# Artemis-Nano.net
KiCad netlist of a schematic drawn in EAGLE
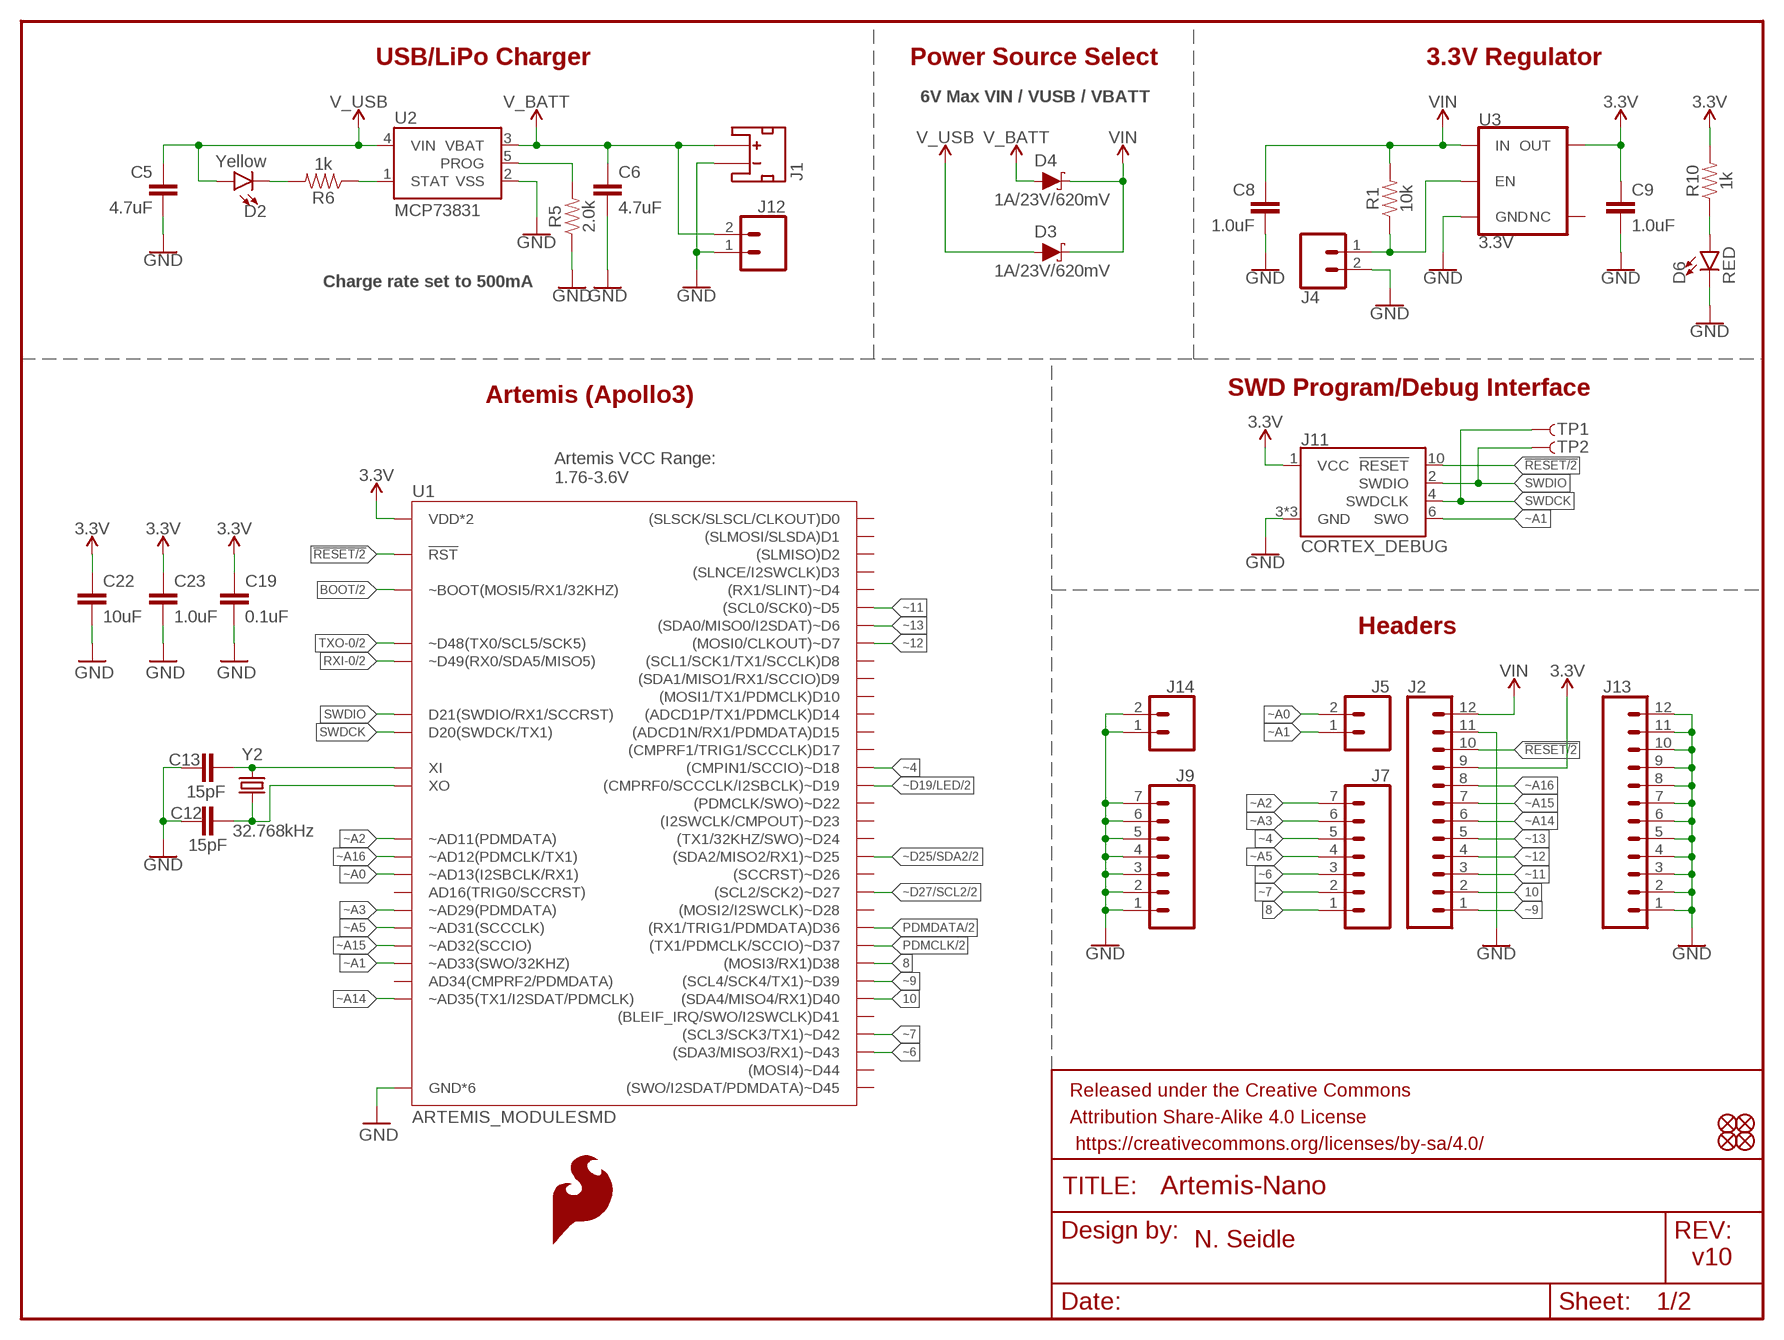
[diagram p0: schematic, sheet 1]
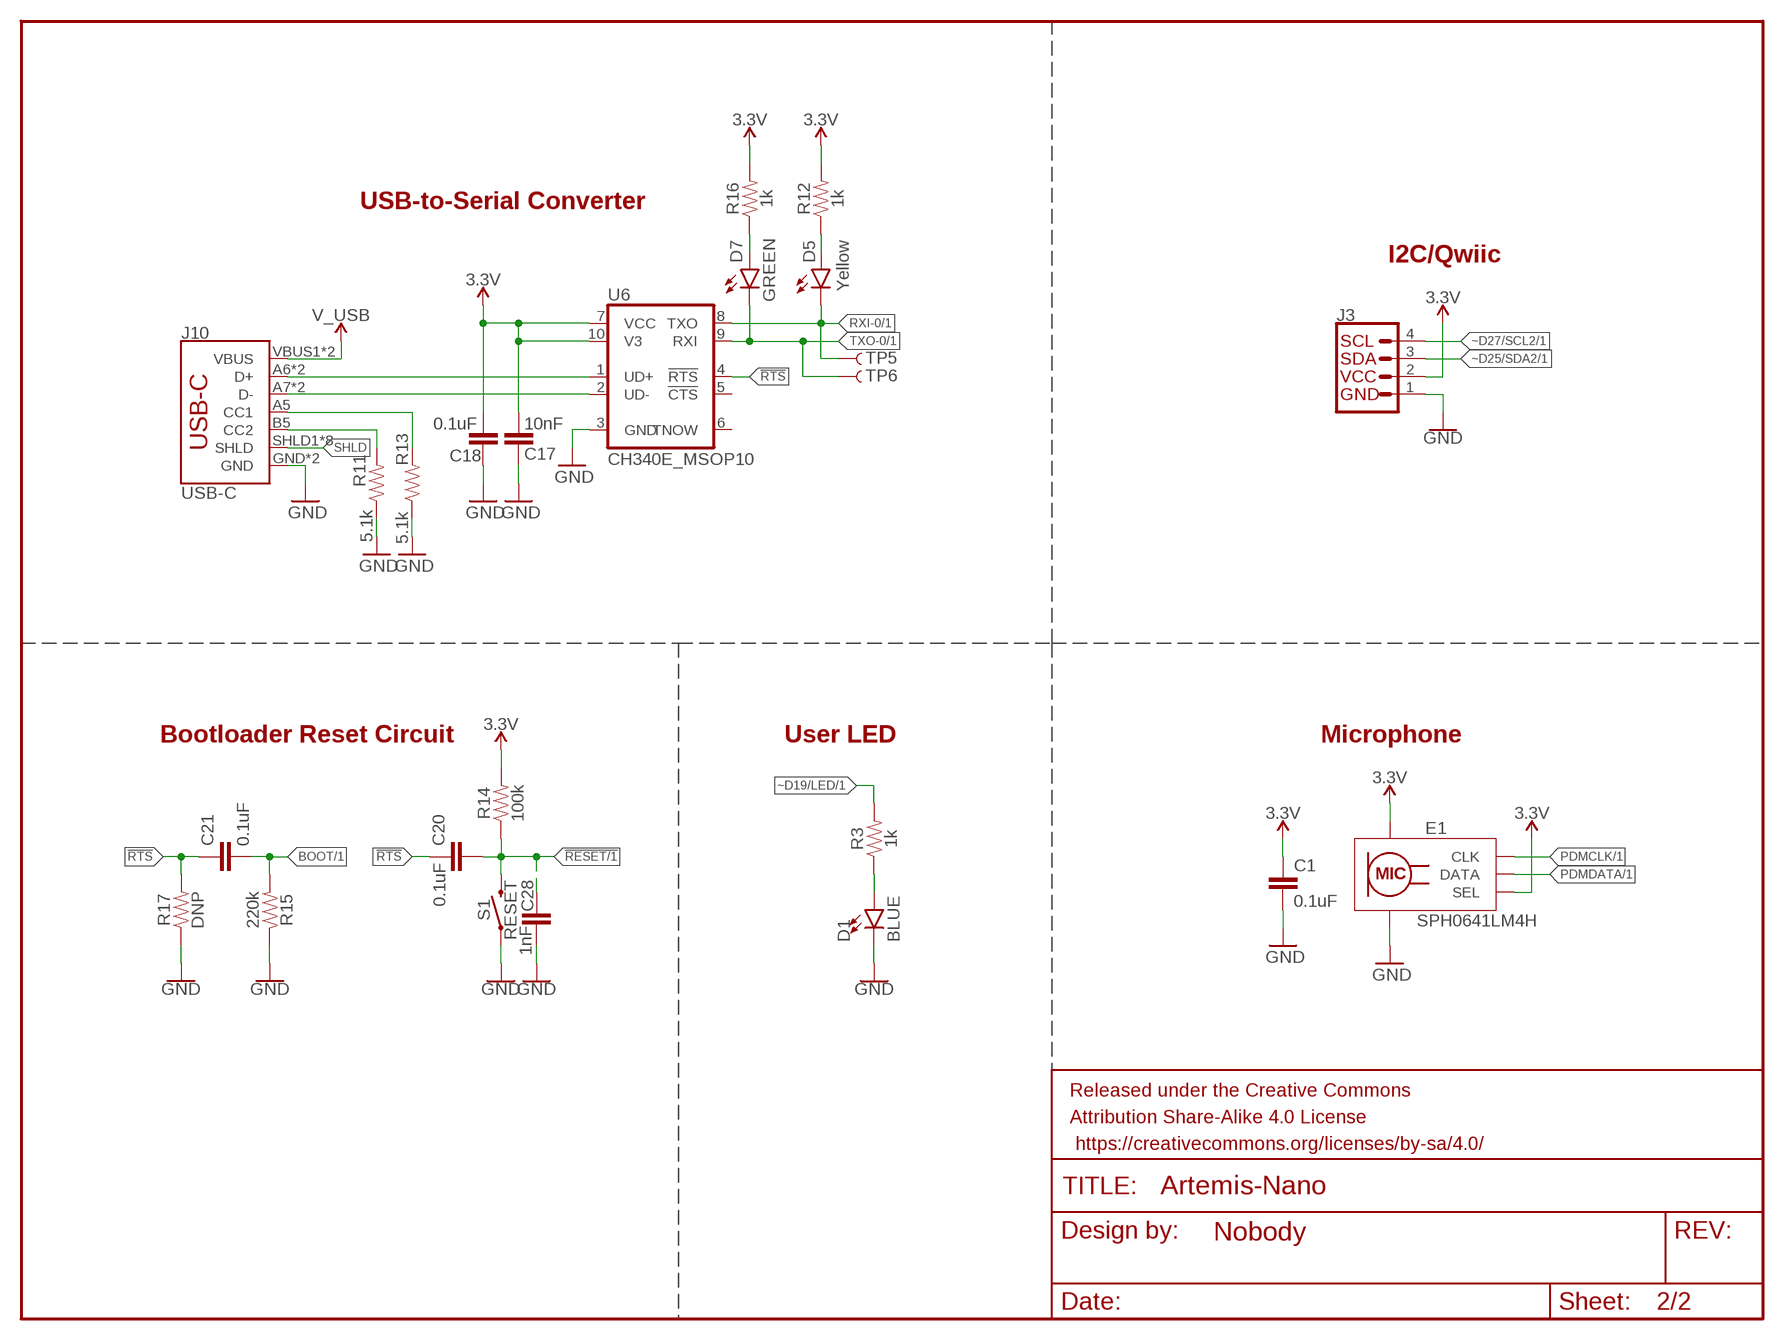
[diagram p1: schematic, sheet 2]

(export (version "E")
  (design (tool "Eeschema 10.0.6"))
  (components
    (comp (ref "C5")
      (value "4.7uF")
      (footprint "eagle-import:0603")
      (libsource (lib "eagle-import") (part "4.7UF-0603-6.3V-(10%)"))
    )
    (comp (ref "C6")
      (value "4.7uF")
      (footprint "eagle-import:0603")
      (libsource (lib "eagle-import") (part "4.7UF-0603-6.3V-(10%)"))
    )
    (comp (ref "C8")
      (value "1.0uF")
      (footprint "eagle-import:0402-TIGHT")
      (libsource (lib "eagle-import") (part "1.0UF-0402T-16V-10%"))
    )
    (comp (ref "C9")
      (value "1.0uF")
      (footprint "eagle-import:0402-TIGHT")
      (libsource (lib "eagle-import") (part "1.0UF-0402T-16V-10%"))
    )
    (comp (ref "C12")
      (value "15pF")
      (footprint "eagle-import:0603")
      (libsource (lib "eagle-import") (part "15PF-0603-50V-5%"))
    )
    (comp (ref "C13")
      (value "15pF")
      (footprint "eagle-import:0603")
      (libsource (lib "eagle-import") (part "15PF-0603-50V-5%"))
    )
    (comp (ref "C19")
      (value "0.1uF")
      (footprint "eagle-import:0402-TIGHT")
      (libsource (lib "eagle-import") (part "0.1UF-0402T-16V-10%"))
    )
    (comp (ref "C22")
      (value "10uF")
      (footprint "eagle-import:0603")
      (libsource (lib "eagle-import") (part "10UF-0603-6.3V-20%"))
    )
    (comp (ref "C23")
      (value "1.0uF")
      (footprint "eagle-import:0402-TIGHT")
      (libsource (lib "eagle-import") (part "1.0UF-0402T-16V-10%"))
    )
    (comp (ref "D2")
      (value "Yellow")
      (footprint "eagle-import:LED-0603")
      (libsource (lib "eagle-import") (part "LED-YELLOW0603"))
    )
    (comp (ref "D3")
      (value "1A/23V/620mV")
      (footprint "eagle-import:SOD-323")
      (libsource (lib "eagle-import") (part "DIODE-SCHOTTKY-BAT20J"))
    )
    (comp (ref "D4")
      (value "1A/23V/620mV")
      (footprint "eagle-import:SOD-323")
      (libsource (lib "eagle-import") (part "DIODE-SCHOTTKY-BAT20J"))
    )
    (comp (ref "D6")
      (value "RED")
      (footprint "eagle-import:LED-0603")
      (libsource (lib "eagle-import") (part "LED-RED0603"))
    )
    (comp (ref "FD1")
      (value "FIDUCIALUFIDUCIAL")
      (footprint "eagle-import:FIDUCIAL-MICRO")
      (libsource (lib "eagle-import") (part "FIDUCIALUFIDUCIAL"))
    )
    (comp (ref "FD2")
      (value "FIDUCIALUFIDUCIAL")
      (footprint "eagle-import:FIDUCIAL-MICRO")
      (libsource (lib "eagle-import") (part "FIDUCIALUFIDUCIAL"))
    )
    (comp (ref "FD3")
      (value "FIDUCIALUFIDUCIAL")
      (footprint "eagle-import:FIDUCIAL-MICRO")
      (libsource (lib "eagle-import") (part "FIDUCIALUFIDUCIAL"))
    )
    (comp (ref "FD4")
      (value "FIDUCIALUFIDUCIAL")
      (footprint "eagle-import:FIDUCIAL-MICRO")
      (libsource (lib "eagle-import") (part "FIDUCIALUFIDUCIAL"))
    )
    (comp (ref "FRAME1")
      (value "FRAME-LETTER")
      (footprint "eagle-import:CREATIVE_COMMONS")
      (libsource (lib "eagle-import") (part "FRAME-LETTER"))
    )
    (comp (ref "J1")
      (value "JST_2MM_MALE")
      (footprint "eagle-import:JST-2-SMD")
      (libsource (lib "eagle-import") (part "JST_2MM_MALE"))
    )
    (comp (ref "J2")
      (value "CONN_12NO_SILK")
      (footprint "eagle-import:1X12_NO_SILK")
      (libsource (lib "eagle-import") (part "CONN_12NO_SILK"))
    )
    (comp (ref "J4")
      (value "CONN_021X02_NO_SILK")
      (footprint "eagle-import:1X02_NO_SILK")
      (libsource (lib "eagle-import") (part "CONN_021X02_NO_SILK"))
    )
    (comp (ref "J5")
      (value "CONN_021X02_NO_SILK")
      (footprint "eagle-import:1X02_NO_SILK")
      (libsource (lib "eagle-import") (part "CONN_021X02_NO_SILK"))
    )
    (comp (ref "J7")
      (value "CONN_07NO_SILK")
      (footprint "eagle-import:1X07_NO_SILK")
      (libsource (lib "eagle-import") (part "CONN_07NO_SILK"))
    )
    (comp (ref "J9")
      (value "CONN_07NO_SILK")
      (footprint "eagle-import:1X07_NO_SILK")
      (libsource (lib "eagle-import") (part "CONN_07NO_SILK"))
    )
    (comp (ref "J11")
      (value "CORTEX_DEBUG")
      (footprint "eagle-import:2X5-PTH-1.27MM-NO_SILK")
      (libsource (lib "eagle-import") (part "CORTEX_DEBUG_MINIMUM_PTH_NS"))
    )
    (comp (ref "J12")
      (value "CONN_021X02_NO_SILK")
      (footprint "eagle-import:1X02_NO_SILK")
      (libsource (lib "eagle-import") (part "CONN_021X02_NO_SILK"))
    )
    (comp (ref "J13")
      (value "CONN_12NO_SILK")
      (footprint "eagle-import:1X12_NO_SILK")
      (libsource (lib "eagle-import") (part "CONN_12NO_SILK"))
    )
    (comp (ref "J14")
      (value "CONN_021X02_NO_SILK")
      (footprint "eagle-import:1X02_NO_SILK")
      (libsource (lib "eagle-import") (part "CONN_021X02_NO_SILK"))
    )
    (comp (ref "LOGO1")
      (value "SFE_LOGO_FLAME.1_INCH")
      (footprint "eagle-import:SFE_LOGO_FLAME_.1")
      (libsource (lib "eagle-import") (part "SFE_LOGO_FLAME.1_INCH"))
    )
    (comp (ref "LOGO4")
      (value "SFE_LOGO_FLAME.1_INCH")
      (footprint "eagle-import:SFE_LOGO_FLAME_.1")
      (libsource (lib "eagle-import") (part "SFE_LOGO_FLAME.1_INCH"))
    )
    (comp (ref "R1")
      (value "10k")
      (footprint "eagle-import:0603")
      (libsource (lib "eagle-import") (part "10KOHM-0603-1/10W-1%"))
    )
    (comp (ref "R5")
      (value "2.0k")
      (footprint "eagle-import:0603")
      (libsource (lib "eagle-import") (part "2.0KOHM-0603-1/10W-5%"))
    )
    (comp (ref "R6")
      (value "1k")
      (footprint "eagle-import:0603")
      (libsource (lib "eagle-import") (part "1KOHM-0603-1/10W-1%"))
    )
    (comp (ref "R10")
      (value "1k")
      (footprint "eagle-import:0603")
      (libsource (lib "eagle-import") (part "1KOHM-0603-1/10W-1%"))
    )
    (comp (ref "TP1")
      (value "TEST-POINT3X5")
      (footprint "eagle-import:PAD.03X.05")
      (libsource (lib "eagle-import") (part "TEST-POINT3X5"))
    )
    (comp (ref "TP2")
      (value "TEST-POINT3X5")
      (footprint "eagle-import:PAD.03X.05")
      (libsource (lib "eagle-import") (part "TEST-POINT3X5"))
    )
    (comp (ref "U1")
      (value "ARTEMIS_MODULESMD")
      (footprint "eagle-import:ARTEMIS_FP")
      (libsource (lib "eagle-import") (part "ARTEMIS_MODULESMD"))
    )
    (comp (ref "U2")
      (value "MCP73831")
      (footprint "eagle-import:SOT23-5")
      (libsource (lib "eagle-import") (part "MCP73831"))
    )
    (comp (ref "U3")
      (value "3.3V")
      (footprint "eagle-import:SOT23-5")
      (libsource (lib "eagle-import") (part "V_REG_AP2112K-3.3V"))
    )
    (comp (ref "Y2")
      (value "32.768kHz")
      (footprint "eagle-import:CRYSTAL-SMD-3.2X1.5MM")
      (libsource (lib "eagle-import") (part "CRYSTAL-32.768KHZSMD-3.2X1.5"))
    )
    (comp (ref "C1")
      (value "0.1uF")
      (footprint "eagle-import:0402-TIGHT")
      (libsource (lib "eagle-import") (part "0.1UF-0402T-16V-10%"))
    )
    (comp (ref "C17")
      (value "10nF")
      (footprint "eagle-import:0603")
      (libsource (lib "eagle-import") (part "10NF-0603-50V-10%"))
    )
    (comp (ref "C18")
      (value "0.1uF")
      (footprint "eagle-import:0603")
      (libsource (lib "eagle-import") (part "0.1UF-0603-25V-(+80/-20%)"))
    )
    (comp (ref "C20")
      (value "0.1uF")
      (footprint "eagle-import:0603")
      (libsource (lib "eagle-import") (part "0.1UF-0603-25V-5%"))
    )
    (comp (ref "C21")
      (value "0.1uF")
      (footprint "eagle-import:0603")
      (libsource (lib "eagle-import") (part "0.1UF-0603-25V-5%"))
    )
    (comp (ref "C28")
      (value "1nF")
      (footprint "eagle-import:0603")
      (libsource (lib "eagle-import") (part "1.0NF/1000PF-0603-50V-10%"))
    )
    (comp (ref "D1")
      (value "BLUE")
      (footprint "eagle-import:LED-0603")
      (libsource (lib "eagle-import") (part "LED-BLUE0603"))
    )
    (comp (ref "D5")
      (value "Yellow")
      (footprint "eagle-import:LED-0603")
      (libsource (lib "eagle-import") (part "LED-YELLOW0603"))
    )
    (comp (ref "D7")
      (value "GREEN")
      (footprint "eagle-import:LED-0603")
      (libsource (lib "eagle-import") (part "LED-GREEN0603"))
    )
    (comp (ref "E1")
      (value "SPH0641LM4H")
      (footprint "eagle-import:SPH0641LM4H-1_MICROPHONE")
      (libsource (lib "eagle-import") (part "SPH0641LM4H-1_MICROPHONE"))
    )
    (comp (ref "FRAME2")
      (value "FRAME-LETTERNO_PACKAGE")
      (footprint "eagle-import:DUMMY")
      (fields (field (name "DESIGNER") "Nobody"))
      (libsource (lib "eagle-import") (part "FRAME-LETTERNO_PACKAGE"))
    )
    (comp (ref "J3")
      (value "QWIIC_CONNECTORJS-1MM")
      (footprint "eagle-import:JST04_1MM_RA")
      (libsource (lib "eagle-import") (part "QWIIC_CONNECTORJS-1MM"))
    )
    (comp (ref "J10")
      (value "USB-C")
      (footprint "eagle-import:USB-C-16P")
      (libsource (lib "eagle-import") (part "USB_C"))
    )
    (comp (ref "R3")
      (value "1k")
      (footprint "eagle-import:0603")
      (libsource (lib "eagle-import") (part "1KOHM-0603-1/10W-1%"))
    )
    (comp (ref "R11")
      (value "5.1k")
      (footprint "eagle-import:0603")
      (libsource (lib "eagle-import") (part "5.1KOHM5.1KOHM-0603-1/10W-1%"))
    )
    (comp (ref "R12")
      (value "1k")
      (footprint "eagle-import:0603")
      (libsource (lib "eagle-import") (part "1KOHM-0603-1/10W-1%"))
    )
    (comp (ref "R13")
      (value "5.1k")
      (footprint "eagle-import:0603")
      (libsource (lib "eagle-import") (part "5.1KOHM5.1KOHM-0603-1/10W-1%"))
    )
    (comp (ref "R14")
      (value "100k")
      (footprint "eagle-import:0603")
      (libsource (lib "eagle-import") (part "100KOHM-0603-1/10W-1%"))
    )
    (comp (ref "R15")
      (value "220k")
      (footprint "eagle-import:0603")
      (libsource (lib "eagle-import") (part "220KOHM-0603-1/10W-1%"))
    )
    (comp (ref "R16")
      (value "1k")
      (footprint "eagle-import:0603")
      (libsource (lib "eagle-import") (part "1KOHM-0603-1/10W-1%"))
    )
    (comp (ref "R17")
      (value "DNP")
      (footprint "eagle-import:0603")
      (libsource (lib "eagle-import") (part "1MOHM-0603-1/4W-5%"))
    )
    (comp (ref "S1")
      (value "RESET")
      (footprint "eagle-import:TACTILE_SWITCH_SMD_4.6X2.8MM")
      (libsource (lib "eagle-import") (part "MOMENTARY-SWITCH-SPST-SMD-4.6X2.8MM"))
    )
    (comp (ref "TP5")
      (value "TEST-POINT3X5")
      (footprint "eagle-import:PAD.03X.05")
      (libsource (lib "eagle-import") (part "TEST-POINT3X5"))
    )
    (comp (ref "TP6")
      (value "TEST-POINT3X5")
      (footprint "eagle-import:PAD.03X.05")
      (libsource (lib "eagle-import") (part "TEST-POINT3X5"))
    )
    (comp (ref "U6")
      (value "CH340E_MSOP10")
      (footprint "eagle-import:MSOP10")
      (libsource (lib "eagle-import") (part "CH340E_MSOP10"))
    )
  )
  (nets
    (net (code "1") (name "3.3V") (class "Default")
      (node (ref "C1") (pin "1") (pinfunction "1_1") (pintype "passive"))
      (node (ref "C17") (pin "1") (pinfunction "1_1") (pintype "passive"))
      (node (ref "C18") (pin "1") (pinfunction "1_1") (pintype "passive"))
      (node (ref "C19") (pin "2") (pinfunction "2_2") (pintype "passive"))
      (node (ref "C22") (pin "1") (pinfunction "1_1") (pintype "passive"))
      (node (ref "C23") (pin "1") (pinfunction "1_1") (pintype "passive"))
      (node (ref "C9") (pin "1") (pinfunction "1_1") (pintype "passive"))
      (node (ref "E1") (pin "2") (pinfunction "SEL_2") (pintype "input"))
      (node (ref "E1") (pin "5") (pinfunction "VDD_5") (pintype "power_in"))
      (node (ref "J11") (pin "1") (pinfunction "VCC_1") (pintype "bidirectional"))
      (node (ref "J2") (pin "9") (pinfunction "9_9") (pintype "passive"))
      (node (ref "J3") (pin "2") (pinfunction "2_2") (pintype "power_in"))
      (node (ref "R10") (pin "2") (pinfunction "2_2") (pintype "passive"))
      (node (ref "R12") (pin "2") (pinfunction "2_2") (pintype "passive"))
      (node (ref "R14") (pin "2") (pinfunction "2_2") (pintype "passive"))
      (node (ref "R16") (pin "2") (pinfunction "2_2") (pintype "passive"))
      (node (ref "U1") (pin "VDD@36") (pinfunction "VDD*2_VDD@36") (pintype "bidirectional"))
      (node (ref "U1") (pin "VDD@37") (pinfunction "VDD*2_VDD@37") (pintype "bidirectional"))
      (node (ref "U3") (pin "5") (pinfunction "OUT_5") (pintype "passive"))
      (node (ref "U6") (pin "10") (pinfunction "V3_10") (pintype "bidirectional"))
      (node (ref "U6") (pin "7") (pinfunction "VCC_7") (pintype "bidirectional"))
    )
    (net (code "2") (name "8") (class "Default")
      (node (ref "J7") (pin "1") (pinfunction "1_1") (pintype "passive"))
      (node (ref "U1") (pin "D38") (pinfunction "(MOSI3/RX1)D38_D38") (pintype "bidirectional"))
    )
    (net (code "3") (name "10") (class "Default")
      (node (ref "J2") (pin "2") (pinfunction "2_2") (pintype "passive"))
      (node (ref "U1") (pin "D40") (pinfunction "(SDA4/MISO4/RX1)D40_D40") (pintype "bidirectional"))
    )
    (net (code "4") (name "BOOT") (class "Default")
      (node (ref "C21") (pin "2") (pinfunction "2_2") (pintype "passive"))
      (node (ref "R15") (pin "2") (pinfunction "2_2") (pintype "passive"))
      (node (ref "U1") (pin "BOOT") (pinfunction "~{BOOT(MOSI5/RX1/32KHZ})_BOOT") (pintype "bidirectional"))
    )
    (net (code "5") (name "GND") (class "Default")
      (node (ref "C1") (pin "2") (pinfunction "2_2") (pintype "passive"))
      (node (ref "C12") (pin "1") (pinfunction "1_1") (pintype "passive"))
      (node (ref "C13") (pin "1") (pinfunction "1_1") (pintype "passive"))
      (node (ref "C17") (pin "2") (pinfunction "2_2") (pintype "passive"))
      (node (ref "C18") (pin "2") (pinfunction "2_2") (pintype "passive"))
      (node (ref "C19") (pin "1") (pinfunction "1_1") (pintype "passive"))
      (node (ref "C22") (pin "2") (pinfunction "2_2") (pintype "passive"))
      (node (ref "C23") (pin "2") (pinfunction "2_2") (pintype "passive"))
      (node (ref "C28") (pin "2") (pinfunction "2_2") (pintype "passive"))
      (node (ref "C5") (pin "2") (pinfunction "2_2") (pintype "passive"))
      (node (ref "C6") (pin "2") (pinfunction "2_2") (pintype "passive"))
      (node (ref "C8") (pin "2") (pinfunction "2_2") (pintype "passive"))
      (node (ref "C9") (pin "2") (pinfunction "2_2") (pintype "passive"))
      (node (ref "D1") (pin "C") (pinfunction "C_C") (pintype "passive"))
      (node (ref "D6") (pin "C") (pinfunction "C_C") (pintype "passive"))
      (node (ref "E1") (pin "3") (pinfunction "GND_3") (pintype "power_in"))
      (node (ref "E1") (pin "6") (pinfunction "GND_6") (pintype "power_in"))
      (node (ref "E1") (pin "7") (pinfunction "GND_7") (pintype "power_in"))
      (node (ref "E1") (pin "8") (pinfunction "GND_8") (pintype "power_in"))
      (node (ref "J1") (pin "1") (pinfunction "-_1") (pintype "bidirectional"))
      (node (ref "J10") (pin "GND") (pinfunction "GND_GND") (pintype "bidirectional"))
      (node (ref "J10") (pin "GND2") (pinfunction "GND_GND2") (pintype "bidirectional"))
      (node (ref "J11") (pin "3") (pinfunction "GND_3") (pintype "bidirectional"))
      (node (ref "J11") (pin "5") (pinfunction "GND_5") (pintype "bidirectional"))
      (node (ref "J11") (pin "9") (pinfunction "GND_9") (pintype "bidirectional"))
      (node (ref "J12") (pin "1") (pinfunction "1_1") (pintype "passive"))
      (node (ref "J13") (pin "1") (pinfunction "1_1") (pintype "passive"))
      (node (ref "J13") (pin "10") (pinfunction "10_10") (pintype "passive"))
      (node (ref "J13") (pin "11") (pinfunction "11_11") (pintype "passive"))
      (node (ref "J13") (pin "12") (pinfunction "12_12") (pintype "passive"))
      (node (ref "J13") (pin "2") (pinfunction "2_2") (pintype "passive"))
      (node (ref "J13") (pin "3") (pinfunction "3_3") (pintype "passive"))
      (node (ref "J13") (pin "4") (pinfunction "4_4") (pintype "passive"))
      (node (ref "J13") (pin "5") (pinfunction "5_5") (pintype "passive"))
      (node (ref "J13") (pin "6") (pinfunction "6_6") (pintype "passive"))
      (node (ref "J13") (pin "7") (pinfunction "7_7") (pintype "passive"))
      (node (ref "J13") (pin "8") (pinfunction "8_8") (pintype "passive"))
      (node (ref "J13") (pin "9") (pinfunction "9_9") (pintype "passive"))
      (node (ref "J14") (pin "1") (pinfunction "1_1") (pintype "passive"))
      (node (ref "J14") (pin "2") (pinfunction "2_2") (pintype "passive"))
      (node (ref "J2") (pin "11") (pinfunction "11_11") (pintype "passive"))
      (node (ref "J3") (pin "1") (pinfunction "1_1") (pintype "power_in"))
      (node (ref "J4") (pin "2") (pinfunction "2_2") (pintype "passive"))
      (node (ref "J9") (pin "1") (pinfunction "1_1") (pintype "passive"))
      (node (ref "J9") (pin "2") (pinfunction "2_2") (pintype "passive"))
      (node (ref "J9") (pin "3") (pinfunction "3_3") (pintype "passive"))
      (node (ref "J9") (pin "4") (pinfunction "4_4") (pintype "passive"))
      (node (ref "J9") (pin "5") (pinfunction "5_5") (pintype "passive"))
      (node (ref "J9") (pin "6") (pinfunction "6_6") (pintype "passive"))
      (node (ref "J9") (pin "7") (pinfunction "7_7") (pintype "passive"))
      (node (ref "R11") (pin "1") (pinfunction "1_1") (pintype "passive"))
      (node (ref "R13") (pin "1") (pinfunction "1_1") (pintype "passive"))
      (node (ref "R15") (pin "1") (pinfunction "1_1") (pintype "passive"))
      (node (ref "R17") (pin "1") (pinfunction "1_1") (pintype "passive"))
      (node (ref "R5") (pin "1") (pinfunction "1_1") (pintype "passive"))
      (node (ref "S1") (pin "1") (pinfunction "1_1") (pintype "passive"))
      (node (ref "S1") (pin "2") (pinfunction "1_2") (pintype "passive"))
      (node (ref "U1") (pin "GND@1") (pinfunction "GND*6_GND@1") (pintype "bidirectional"))
      (node (ref "U1") (pin "GND@22") (pinfunction "GND*6_GND@22") (pintype "bidirectional"))
      (node (ref "U1") (pin "GND@38") (pinfunction "GND*6_GND@38") (pintype "bidirectional"))
      (node (ref "U1") (pin "GND@39") (pinfunction "GND*6_GND@39") (pintype "bidirectional"))
      (node (ref "U1") (pin "GND@47") (pinfunction "GND*6_GND@47") (pintype "bidirectional"))
      (node (ref "U1") (pin "GND@59") (pinfunction "GND*6_GND@59") (pintype "bidirectional"))
      (node (ref "U2") (pin "2") (pinfunction "VSS_2") (pintype "power_in"))
      (node (ref "U3") (pin "2") (pinfunction "GND_2") (pintype "input"))
      (node (ref "U6") (pin "3") (pinfunction "GND_3") (pintype "bidirectional"))
    )
    (net (code "6") (name "Net-(D1-PadA)") (class "Default")
      (node (ref "D1") (pin "A") (pinfunction "A_A") (pintype "passive"))
      (node (ref "R3") (pin "1") (pinfunction "1_1") (pintype "passive"))
    )
    (net (code "7") (name "Net-(D2-PadC)") (class "Default")
      (node (ref "D2") (pin "C") (pinfunction "C_C") (pintype "passive"))
      (node (ref "R6") (pin "2") (pinfunction "2_2") (pintype "passive"))
    )
    (net (code "8") (name "Net-(D5-PadA)") (class "Default")
      (node (ref "D5") (pin "A") (pinfunction "A_A") (pintype "passive"))
      (node (ref "R12") (pin "1") (pinfunction "1_1") (pintype "passive"))
    )
    (net (code "9") (name "Net-(D6-PadA)") (class "Default")
      (node (ref "D6") (pin "A") (pinfunction "A_A") (pintype "passive"))
      (node (ref "R10") (pin "1") (pinfunction "1_1") (pintype "passive"))
    )
    (net (code "10") (name "Net-(D7-PadA)") (class "Default")
      (node (ref "D7") (pin "A") (pinfunction "A_A") (pintype "passive"))
      (node (ref "R16") (pin "1") (pinfunction "1_1") (pintype "passive"))
    )
    (net (code "11") (name "Net-(J10-CC1)") (class "Default")
      (node (ref "J10") (pin "A5") (pinfunction "CC1_A5") (pintype "bidirectional"))
      (node (ref "R13") (pin "2") (pinfunction "2_2") (pintype "passive"))
    )
    (net (code "12") (name "Net-(J10-CC2)") (class "Default")
      (node (ref "J10") (pin "B5") (pinfunction "CC2_B5") (pintype "bidirectional"))
      (node (ref "R11") (pin "2") (pinfunction "2_2") (pintype "passive"))
    )
    (net (code "13") (name "Net-(U2-PROG)") (class "Default")
      (node (ref "R5") (pin "2") (pinfunction "2_2") (pintype "passive"))
      (node (ref "U2") (pin "5") (pinfunction "PROG_5") (pintype "input"))
    )
    (net (code "14") (name "Net-(U2-STAT)") (class "Default")
      (node (ref "R6") (pin "1") (pinfunction "1_1") (pintype "passive"))
      (node (ref "U2") (pin "1") (pinfunction "STAT_1") (pintype "output"))
    )
    (net (code "15") (name "Net-(U3-EN)") (class "Default")
      (node (ref "J4") (pin "1") (pinfunction "1_1") (pintype "passive"))
      (node (ref "R1") (pin "1") (pinfunction "1_1") (pintype "passive"))
      (node (ref "U3") (pin "3") (pinfunction "EN_3") (pintype "input"))
    )
    (net (code "16") (name "Net-(U6-UD+)") (class "Default")
      (node (ref "J10") (pin "A6") (pinfunction "D+_A6") (pintype "bidirectional"))
      (node (ref "J10") (pin "B6") (pinfunction "D+_B6") (pintype "bidirectional"))
      (node (ref "U6") (pin "1") (pinfunction "UD+_1") (pintype "bidirectional"))
    )
    (net (code "17") (name "Net-(U6-UD-)") (class "Default")
      (node (ref "J10") (pin "A7") (pinfunction "D-_A7") (pintype "bidirectional"))
      (node (ref "J10") (pin "B7") (pinfunction "D-_B7") (pintype "bidirectional"))
      (node (ref "U6") (pin "2") (pinfunction "UD-_2") (pintype "bidirectional"))
    )
    (net (code "18") (name "Net-(Y2-1)") (class "Default")
      (node (ref "C13") (pin "2") (pinfunction "2_2") (pintype "passive"))
      (node (ref "U1") (pin "XI") (pinfunction "XI_XI") (pintype "bidirectional"))
      (node (ref "Y2") (pin "P$1") (pinfunction "1_P$1") (pintype "passive"))
    )
    (net (code "19") (name "Net-(Y2-2)") (class "Default")
      (node (ref "C12") (pin "2") (pinfunction "2_2") (pintype "passive"))
      (node (ref "U1") (pin "XO") (pinfunction "XO_XO") (pintype "bidirectional"))
      (node (ref "Y2") (pin "P$2") (pinfunction "2_P$2") (pintype "passive"))
    )
    (net (code "20") (name "PDMCLK") (class "Default")
      (node (ref "E1") (pin "4") (pinfunction "CLK_4") (pintype "input"))
      (node (ref "U1") (pin "~D37") (pinfunction "(TX1/PDMCLK/SCCIO)~{D37}_~D37") (pintype "bidirectional"))
    )
    (net (code "21") (name "PDMDATA") (class "Default")
      (node (ref "E1") (pin "1") (pinfunction "DATA_1") (pintype "output"))
      (node (ref "U1") (pin "D36") (pinfunction "(RX1/TRIG1/PDMDATA)D36_D36") (pintype "bidirectional"))
    )
    (net (code "22") (name "RXI-0") (class "Default")
      (node (ref "D5") (pin "C") (pinfunction "C_C") (pintype "passive"))
      (node (ref "TP5") (pin "P$1") (pinfunction "1_P$1") (pintype "bidirectional"))
      (node (ref "U1") (pin "RXI-0") (pinfunction "~{D49(RX0/SDA5/MISO5})_RXI-0") (pintype "bidirectional"))
      (node (ref "U6") (pin "8") (pinfunction "TXO_8") (pintype "bidirectional"))
    )
    (net (code "23") (name "SHLD") (class "Default")
      (node (ref "J10") (pin "SHLD1") (pinfunction "SHLD_SHLD1") (pintype "bidirectional"))
      (node (ref "J10") (pin "SHLD2") (pinfunction "SHLD_SHLD2") (pintype "bidirectional"))
      (node (ref "J10") (pin "SHLD3") (pinfunction "SHLD_SHLD3") (pintype "bidirectional"))
      (node (ref "J10") (pin "SHLD4") (pinfunction "SHLD_SHLD4") (pintype "bidirectional"))
      (node (ref "J10") (pin "SHLD5") (pinfunction "SHLD_SHLD5") (pintype "bidirectional"))
      (node (ref "J10") (pin "SHLD6") (pinfunction "SHLD_SHLD6") (pintype "bidirectional"))
      (node (ref "J10") (pin "SHLD7") (pinfunction "SHLD_SHLD7") (pintype "bidirectional"))
      (node (ref "J10") (pin "SHLD8") (pinfunction "SHLD_SHLD8") (pintype "bidirectional"))
    )
    (net (code "24") (name "SWDCK") (class "Default")
      (node (ref "J11") (pin "4") (pinfunction "SWDCLK_4") (pintype "bidirectional"))
      (node (ref "TP1") (pin "P$1") (pinfunction "1_P$1") (pintype "bidirectional"))
      (node (ref "U1") (pin "SWDCK") (pinfunction "D20(SWDCK/TX1)_SWDCK") (pintype "bidirectional"))
    )
    (net (code "25") (name "SWDIO") (class "Default")
      (node (ref "J11") (pin "2") (pinfunction "SWDIO_2") (pintype "bidirectional"))
      (node (ref "TP2") (pin "P$1") (pinfunction "1_P$1") (pintype "bidirectional"))
      (node (ref "U1") (pin "SWDIO") (pinfunction "D21(SWDIO/RX1/SCCRST)_SWDIO") (pintype "bidirectional"))
    )
    (net (code "26") (name "TXO-0") (class "Default")
      (node (ref "D7") (pin "C") (pinfunction "C_C") (pintype "passive"))
      (node (ref "TP6") (pin "P$1") (pinfunction "1_P$1") (pintype "bidirectional"))
      (node (ref "U1") (pin "TXO-0") (pinfunction "~{D48(TX0/SCL5/SCK5})_TXO-0") (pintype "bidirectional"))
      (node (ref "U6") (pin "9") (pinfunction "RXI_9") (pintype "bidirectional"))
    )
    (net (code "27") (name "VIN") (class "Default")
      (node (ref "C8") (pin "1") (pinfunction "1_1") (pintype "passive"))
      (node (ref "D3") (pin "C") (pinfunction "C_C") (pintype "passive"))
      (node (ref "D4") (pin "C") (pinfunction "C_C") (pintype "passive"))
      (node (ref "J2") (pin "12") (pinfunction "12_12") (pintype "passive"))
      (node (ref "R1") (pin "2") (pinfunction "2_2") (pintype "passive"))
      (node (ref "U3") (pin "1") (pinfunction "IN_1") (pintype "input"))
    )
    (net (code "28") (name "V_BATT") (class "Default")
      (node (ref "C6") (pin "1") (pinfunction "1_1") (pintype "passive"))
      (node (ref "D4") (pin "A") (pinfunction "A_A") (pintype "passive"))
      (node (ref "J1") (pin "2") (pinfunction "+_2") (pintype "bidirectional"))
      (node (ref "J12") (pin "2") (pinfunction "2_2") (pintype "passive"))
      (node (ref "U2") (pin "3") (pinfunction "VBAT_3") (pintype "power_in"))
    )
    (net (code "29") (name "V_USB") (class "Default")
      (node (ref "C5") (pin "1") (pinfunction "1_1") (pintype "passive"))
      (node (ref "D2") (pin "A") (pinfunction "A_A") (pintype "passive"))
      (node (ref "D3") (pin "A") (pinfunction "A_A") (pintype "passive"))
      (node (ref "J10") (pin "VBUS1") (pinfunction "VBUS_VBUS1") (pintype "bidirectional"))
      (node (ref "J10") (pin "VBUS2") (pinfunction "VBUS_VBUS2") (pintype "bidirectional"))
      (node (ref "U2") (pin "4") (pinfunction "VIN_4") (pintype "power_in"))
    )
    (net (code "30") (name "unconnected-(J1-PAD1-PadNC1)") (class "Default")
      (node (ref "J1") (pin "NC1") (pinfunction "PAD1_NC1") (pintype "bidirectional"))
    )
    (net (code "31") (name "unconnected-(J1-PAD2-PadNC2)") (class "Default")
      (node (ref "J1") (pin "NC2") (pinfunction "PAD2_NC2") (pintype "bidirectional"))
    )
    (net (code "32") (name "unconnected-(U1-(ADCD1N{slash}RX1{slash}PDMDATA)D15-PadD15)") (class "Default")
      (node (ref "U1") (pin "D15") (pinfunction "(ADCD1N/RX1/PDMDATA)D15_D15") (pintype "bidirectional"))
    )
    (net (code "33") (name "unconnected-(U1-(ADCD1P{slash}TX1{slash}PDMCLK)D14-PadD14)") (class "Default")
      (node (ref "U1") (pin "D14") (pinfunction "(ADCD1P/TX1/PDMCLK)D14_D14") (pintype "bidirectional"))
    )
    (net (code "34") (name "unconnected-(U1-(BLEIF_IRQ{slash}SWO{slash}I2SWCLK)D41-PadD41)") (class "Default")
      (node (ref "U1") (pin "D41") (pinfunction "(BLEIF_IRQ/SWO/I2SWCLK)D41_D41") (pintype "bidirectional"))
    )
    (net (code "35") (name "unconnected-(U1-(CMPRF1{slash}TRIG1{slash}SCCCLK)D17-PadD17)") (class "Default")
      (node (ref "U1") (pin "D17") (pinfunction "(CMPRF1/TRIG1/SCCCLK)D17_D17") (pintype "bidirectional"))
    )
    (net (code "36") (name "unconnected-(U1-(I2SWCLK{slash}CMPOUT)~{D23}-Pad~D23)") (class "Default")
      (node (ref "U1") (pin "~D23") (pinfunction "(I2SWCLK/CMPOUT)~{D23}_~D23") (pintype "bidirectional"))
    )
    (net (code "37") (name "unconnected-(U1-(MOSI1{slash}TX1{slash}PDMCLK)D10-PadD10)") (class "Default")
      (node (ref "U1") (pin "D10") (pinfunction "(MOSI1/TX1/PDMCLK)D10_D10") (pintype "bidirectional"))
    )
    (net (code "38") (name "unconnected-(U1-(MOSI2{slash}I2SWCLK)~{D28}-Pad~D28)") (class "Default")
      (node (ref "U1") (pin "~D28") (pinfunction "(MOSI2/I2SWCLK)~{D28}_~D28") (pintype "bidirectional"))
    )
    (net (code "39") (name "unconnected-(U1-(MOSI4)~{D44}-Pad~D44)") (class "Default")
      (node (ref "U1") (pin "~D44") (pinfunction "(MOSI4)~{D44}_~D44") (pintype "bidirectional"))
    )
    (net (code "40") (name "unconnected-(U1-(PDMCLK{slash}SWO)~{D22}-Pad~D22)") (class "Default")
      (node (ref "U1") (pin "~D22") (pinfunction "(PDMCLK/SWO)~{D22}_~D22") (pintype "bidirectional"))
    )
    (net (code "41") (name "unconnected-(U1-(RX1{slash}SLINT)~{D4}-Pad~D4)") (class "Default")
      (node (ref "U1") (pin "~D4") (pinfunction "(RX1/SLINT)~{D4}_~D4") (pintype "bidirectional"))
    )
    (net (code "42") (name "unconnected-(U1-(SCCRST)~{D26}-Pad~D26)") (class "Default")
      (node (ref "U1") (pin "~D26") (pinfunction "(SCCRST)~{D26}_~D26") (pintype "bidirectional"))
    )
    (net (code "43") (name "unconnected-(U1-(SCL1{slash}SCK1{slash}TX1{slash}SCCLK)D8-PadD8)") (class "Default")
      (node (ref "U1") (pin "D8") (pinfunction "(SCL1/SCK1/TX1/SCCLK)D8_D8") (pintype "bidirectional"))
    )
    (net (code "44") (name "unconnected-(U1-(SDA1{slash}MISO1{slash}RX1{slash}SCCIO)D9-PadD9)") (class "Default")
      (node (ref "U1") (pin "D9") (pinfunction "(SDA1/MISO1/RX1/SCCIO)D9_D9") (pintype "bidirectional"))
    )
    (net (code "45") (name "unconnected-(U1-(SLMISO)D2-PadD2)") (class "Default")
      (node (ref "U1") (pin "D2") (pinfunction "(SLMISO)D2_D2") (pintype "bidirectional"))
    )
    (net (code "46") (name "unconnected-(U1-(SLMOSI{slash}SLSDA)D1-PadD1)") (class "Default")
      (node (ref "U1") (pin "D1") (pinfunction "(SLMOSI/SLSDA)D1_D1") (pintype "bidirectional"))
    )
    (net (code "47") (name "unconnected-(U1-(SLNCE{slash}I2SWCLK)D3-PadD3)") (class "Default")
      (node (ref "U1") (pin "D3") (pinfunction "(SLNCE/I2SWCLK)D3_D3") (pintype "bidirectional"))
    )
    (net (code "48") (name "unconnected-(U1-(SLSCK{slash}SLSCL{slash}CLKOUT)D0-PadD0)") (class "Default")
      (node (ref "U1") (pin "D0") (pinfunction "(SLSCK/SLSCL/CLKOUT)D0_D0") (pintype "bidirectional"))
    )
    (net (code "49") (name "unconnected-(U1-(SWO{slash}I2SDAT{slash}PDMDATA)~{D45}-Pad~D45)") (class "Default")
      (node (ref "U1") (pin "~D45") (pinfunction "(SWO/I2SDAT/PDMDATA)~{D45}_~D45") (pintype "bidirectional"))
    )
    (net (code "50") (name "unconnected-(U1-(TX1{slash}32KHZ{slash}SWO)~{D24}-Pad~D24)") (class "Default")
      (node (ref "U1") (pin "~D24") (pinfunction "(TX1/32KHZ/SWO)~{D24}_~D24") (pintype "bidirectional"))
    )
    (net (code "51") (name "unconnected-(U1-AD16(TRIG0{slash}SCCRST)-PadAD16)") (class "Default")
      (node (ref "U1") (pin "AD16") (pinfunction "AD16(TRIG0/SCCRST)_AD16") (pintype "bidirectional"))
    )
    (net (code "52") (name "unconnected-(U1-AD34(CMPRF2{slash}PDMDATA)-PadAD34)") (class "Default")
      (node (ref "U1") (pin "AD34") (pinfunction "AD34(CMPRF2/PDMDATA)_AD34") (pintype "bidirectional"))
    )
    (net (code "53") (name "unconnected-(U3-NC-Pad4)") (class "Default")
      (node (ref "U3") (pin "4") (pinfunction "NC_4") (pintype "no_connect"))
    )
    (net (code "54") (name "unconnected-(U6-TNOW-Pad6)") (class "Default")
      (node (ref "U6") (pin "6") (pinfunction "TNOW_6") (pintype "bidirectional"))
    )
    (net (code "55") (name "unconnected-(U6-~{CTS}-Pad5)") (class "Default")
      (node (ref "U6") (pin "5") (pinfunction "~{CTS}_5") (pintype "bidirectional"))
    )
    (net (code "56") (name "~{4}") (class "Default")
      (node (ref "J7") (pin "5") (pinfunction "5_5") (pintype "passive"))
      (node (ref "U1") (pin "~D18") (pinfunction "(CMPIN1/SCCIO)~{D18}_~D18") (pintype "bidirectional"))
    )
    (net (code "57") (name "~{6}") (class "Default")
      (node (ref "J7") (pin "3") (pinfunction "3_3") (pintype "passive"))
      (node (ref "U1") (pin "~D43") (pinfunction "(SDA3/MISO3/RX1)~{D43}_~D43") (pintype "bidirectional"))
    )
    (net (code "58") (name "~{7}") (class "Default")
      (node (ref "J7") (pin "2") (pinfunction "2_2") (pintype "passive"))
      (node (ref "U1") (pin "~D42") (pinfunction "(SCL3/SCK3/TX1)~{D42}_~D42") (pintype "bidirectional"))
    )
    (net (code "59") (name "~{9}") (class "Default")
      (node (ref "J2") (pin "1") (pinfunction "1_1") (pintype "passive"))
      (node (ref "U1") (pin "~D39") (pinfunction "(SCL4/SCK4/TX1)~{D39}_~D39") (pintype "bidirectional"))
    )
    (net (code "60") (name "~{11}") (class "Default")
      (node (ref "J2") (pin "3") (pinfunction "3_3") (pintype "passive"))
      (node (ref "U1") (pin "~D5") (pinfunction "(SCL0/SCK0)~{D5}_~D5") (pintype "bidirectional"))
    )
    (net (code "61") (name "~{12}") (class "Default")
      (node (ref "J2") (pin "4") (pinfunction "4_4") (pintype "passive"))
      (node (ref "U1") (pin "D7") (pinfunction "(MOSI0/CLKOUT)~{D7}_D7") (pintype "bidirectional"))
    )
    (net (code "62") (name "~{13}") (class "Default")
      (node (ref "J2") (pin "5") (pinfunction "5_5") (pintype "passive"))
      (node (ref "U1") (pin "~D6") (pinfunction "(SDA0/MISO0/I2SDAT)~{D6}_~D6") (pintype "bidirectional"))
    )
    (net (code "63") (name "~{A0}") (class "Default")
      (node (ref "J5") (pin "2") (pinfunction "2_2") (pintype "passive"))
      (node (ref "U1") (pin "~AD13") (pinfunction "~{AD13(I2SBCLK/RX1})_~AD13") (pintype "bidirectional"))
    )
    (net (code "64") (name "~{A1}") (class "Default")
      (node (ref "J11") (pin "6") (pinfunction "SWO_6") (pintype "bidirectional"))
      (node (ref "J5") (pin "1") (pinfunction "1_1") (pintype "passive"))
      (node (ref "U1") (pin "~AD33/SWO") (pinfunction "~{AD33(SWO/32KHZ})_~AD33/SWO") (pintype "bidirectional"))
    )
    (net (code "65") (name "~{A2}") (class "Default")
      (node (ref "J7") (pin "7") (pinfunction "7_7") (pintype "passive"))
      (node (ref "U1") (pin "~AD11") (pinfunction "~{AD11(PDMDATA})_~AD11") (pintype "bidirectional"))
    )
    (net (code "66") (name "~{A3}") (class "Default")
      (node (ref "J7") (pin "6") (pinfunction "6_6") (pintype "passive"))
      (node (ref "U1") (pin "~AD29") (pinfunction "~{AD29(PDMDATA})_~AD29") (pintype "bidirectional"))
    )
    (net (code "67") (name "~{A5}") (class "Default")
      (node (ref "J7") (pin "4") (pinfunction "4_4") (pintype "passive"))
      (node (ref "U1") (pin "~AD31") (pinfunction "~{AD31(SCCCLK})_~AD31") (pintype "bidirectional"))
    )
    (net (code "68") (name "~{A14}") (class "Default")
      (node (ref "J2") (pin "6") (pinfunction "6_6") (pintype "passive"))
      (node (ref "U1") (pin "~AD35") (pinfunction "~{AD35(TX1/I2SDAT/PDMCLK})_~AD35") (pintype "bidirectional"))
    )
    (net (code "69") (name "~{A15}") (class "Default")
      (node (ref "J2") (pin "7") (pinfunction "7_7") (pintype "passive"))
      (node (ref "U1") (pin "~AD32") (pinfunction "~{AD32(SCCIO})_~AD32") (pintype "bidirectional"))
    )
    (net (code "70") (name "~{A16}") (class "Default")
      (node (ref "J2") (pin "8") (pinfunction "8_8") (pintype "passive"))
      (node (ref "U1") (pin "~AD12") (pinfunction "~{AD12(PDMCLK/TX1})_~AD12") (pintype "bidirectional"))
    )
    (net (code "71") (name "~{D19{slash}LED}") (class "Default")
      (node (ref "R3") (pin "2") (pinfunction "2_2") (pintype "passive"))
      (node (ref "U1") (pin "~D19") (pinfunction "(CMPRF0/SCCCLK/I2SBCLK)~{D19}_~D19") (pintype "bidirectional"))
    )
    (net (code "72") (name "~{D25{slash}SDA2}") (class "Default")
      (node (ref "J3") (pin "3") (pinfunction "3_3") (pintype "passive"))
      (node (ref "U1") (pin "~D25") (pinfunction "(SDA2/MISO2/RX1)~{D25}_~D25") (pintype "bidirectional"))
    )
    (net (code "73") (name "~{D27{slash}SCL2}") (class "Default")
      (node (ref "J3") (pin "4") (pinfunction "4_4") (pintype "passive"))
      (node (ref "U1") (pin "~D27") (pinfunction "(SCL2/SCK2)~{D27}_~D27") (pintype "bidirectional"))
    )
    (net (code "74") (name "~{RESET}") (class "Default")
      (node (ref "C20") (pin "2") (pinfunction "2_2") (pintype "passive"))
      (node (ref "C28") (pin "1") (pinfunction "1_1") (pintype "passive"))
      (node (ref "J11") (pin "10") (pinfunction "~{RESET}_10") (pintype "bidirectional"))
      (node (ref "J2") (pin "10") (pinfunction "10_10") (pintype "passive"))
      (node (ref "R14") (pin "1") (pinfunction "1_1") (pintype "passive"))
      (node (ref "S1") (pin "3") (pinfunction "2_3") (pintype "passive"))
      (node (ref "S1") (pin "4") (pinfunction "2_4") (pintype "passive"))
      (node (ref "U1") (pin "~RST") (pinfunction "~{RST}_~RST") (pintype "bidirectional"))
    )
    (net (code "75") (name "~{RTS}") (class "Default")
      (node (ref "C20") (pin "1") (pinfunction "1_1") (pintype "passive"))
      (node (ref "C21") (pin "1") (pinfunction "1_1") (pintype "passive"))
      (node (ref "R17") (pin "2") (pinfunction "2_2") (pintype "passive"))
      (node (ref "U6") (pin "4") (pinfunction "~{RTS}_4") (pintype "bidirectional"))
    )
  )
)
